# PSoC_PyunPyun_Mini.net
KiCad netlist of a schematic drawn in EAGLE
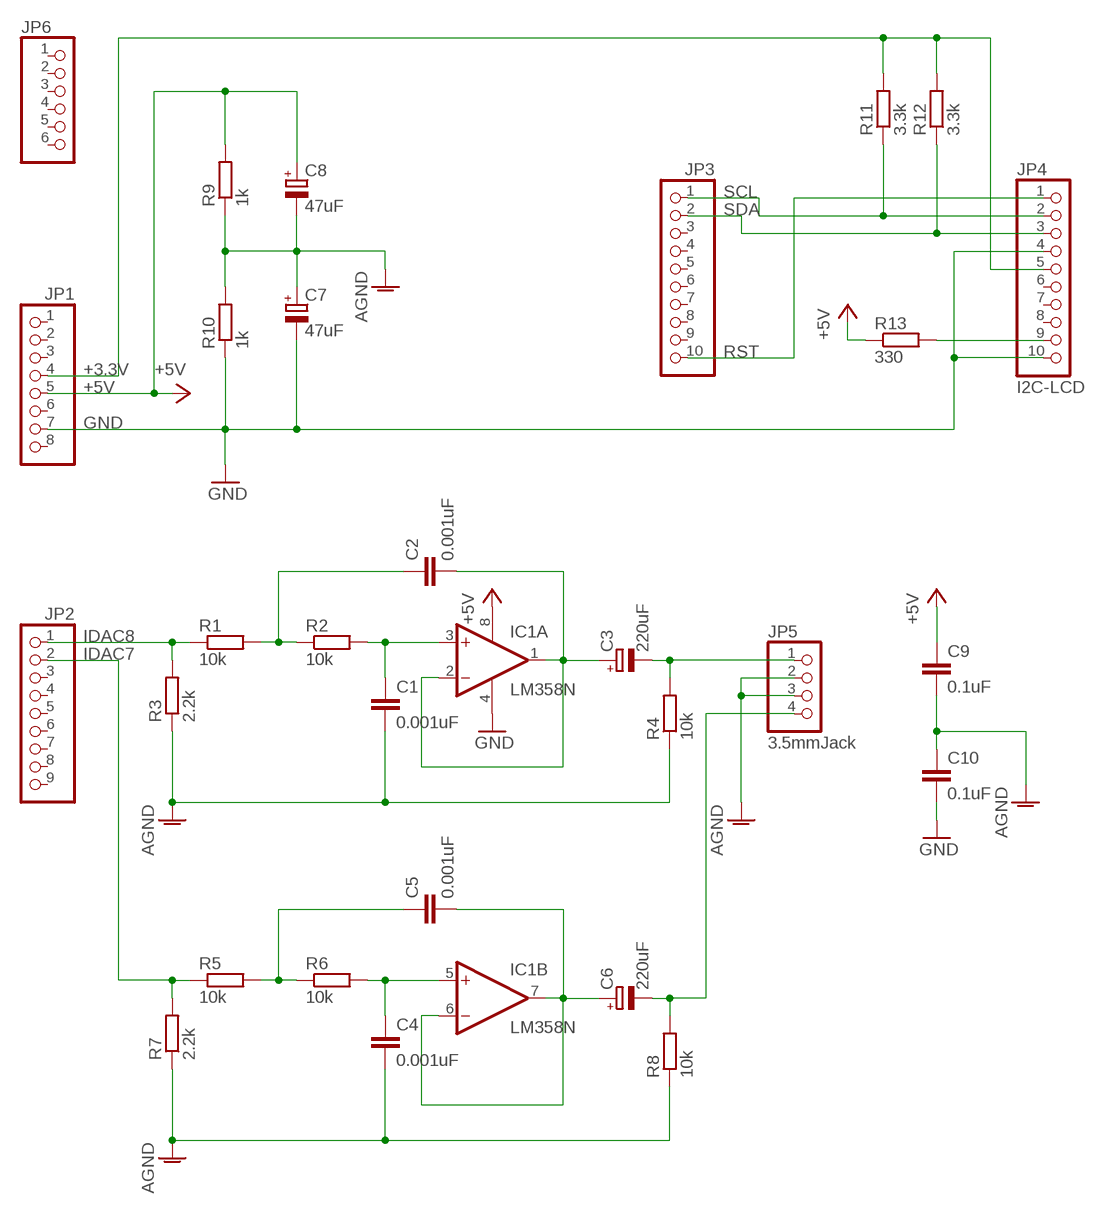
[diagram p0: schematic, sheet 1]

(export (version "E")
  (design (tool "Eeschema 10.0.6"))
  (components
    (comp (ref "C1")
      (value "0.001uF")
      (footprint "eagle-import:C050-024X044")
      (libsource (lib "eagle-import") (part "C-EU050-024X044"))
    )
    (comp (ref "C2")
      (value "0.001uF")
      (footprint "eagle-import:C050-024X044")
      (libsource (lib "eagle-import") (part "C-EU050-024X044"))
    )
    (comp (ref "C3")
      (value "220uF")
      (footprint "eagle-import:E5-8,5")
      (libsource (lib "eagle-import") (part "CPOL-EUE5-8.5"))
    )
    (comp (ref "C4")
      (value "0.001uF")
      (footprint "eagle-import:C050-024X044")
      (libsource (lib "eagle-import") (part "C-EU050-024X044"))
    )
    (comp (ref "C5")
      (value "0.001uF")
      (footprint "eagle-import:C050-024X044")
      (libsource (lib "eagle-import") (part "C-EU050-024X044"))
    )
    (comp (ref "C6")
      (value "220uF")
      (footprint "eagle-import:E5-8,5")
      (libsource (lib "eagle-import") (part "CPOL-EUE5-8.5"))
    )
    (comp (ref "C7")
      (value "47uF")
      (footprint "eagle-import:E5-5")
      (libsource (lib "eagle-import") (part "CPOL-EUE5-5"))
    )
    (comp (ref "C8")
      (value "47uF")
      (footprint "eagle-import:E5-5")
      (libsource (lib "eagle-import") (part "CPOL-EUE5-5"))
    )
    (comp (ref "C9")
      (value "0.1uF")
      (footprint "eagle-import:C050-024X044")
      (libsource (lib "eagle-import") (part "C-EU050-024X044"))
    )
    (comp (ref "C10")
      (value "0.1uF")
      (footprint "eagle-import:C050-024X044")
      (libsource (lib "eagle-import") (part "C-EU050-024X044"))
    )
    (comp (ref "IC1")
      (value "LM358N")
      (footprint "eagle-import:DIL08")
      (libsource (lib "eagle-import") (part "LM358N"))
    )
    (comp (ref "JP1")
      (value "PINHD-1X8")
      (footprint "eagle-import:1X08")
      (libsource (lib "eagle-import") (part "PINHD-1X8"))
    )
    (comp (ref "JP2")
      (value "PINHD-1X9")
      (footprint "eagle-import:1X09")
      (libsource (lib "eagle-import") (part "PINHD-1X9"))
    )
    (comp (ref "JP3")
      (value "PINHD-1X10")
      (footprint "eagle-import:1X10")
      (libsource (lib "eagle-import") (part "PINHD-1X10"))
    )
    (comp (ref "JP4")
      (value "I2C-LCD")
      (footprint "eagle-import:1X10")
      (libsource (lib "eagle-import") (part "PINHD-1X10"))
    )
    (comp (ref "JP5")
      (value "3.5mmJack")
      (footprint "eagle-import:1X04")
      (libsource (lib "eagle-import") (part "PINHD-1X4"))
    )
    (comp (ref "JP6")
      (value "PINHD-1X6")
      (footprint "eagle-import:1X06")
      (libsource (lib "eagle-import") (part "PINHD-1X6"))
    )
    (comp (ref "R1")
      (value "10k")
      (footprint "eagle-import:0207_7")
      (libsource (lib "eagle-import") (part "R-EU_0207/7"))
    )
    (comp (ref "R2")
      (value "10k")
      (footprint "eagle-import:0207_7")
      (libsource (lib "eagle-import") (part "R-EU_0207/7"))
    )
    (comp (ref "R3")
      (value "2.2k")
      (footprint "eagle-import:0207_7")
      (libsource (lib "eagle-import") (part "R-EU_0207/7"))
    )
    (comp (ref "R4")
      (value "10k")
      (footprint "eagle-import:0207_7")
      (libsource (lib "eagle-import") (part "R-EU_0207/7"))
    )
    (comp (ref "R5")
      (value "10k")
      (footprint "eagle-import:0207_7")
      (libsource (lib "eagle-import") (part "R-EU_0207/7"))
    )
    (comp (ref "R6")
      (value "10k")
      (footprint "eagle-import:0207_7")
      (libsource (lib "eagle-import") (part "R-EU_0207/7"))
    )
    (comp (ref "R7")
      (value "2.2k")
      (footprint "eagle-import:0207_7")
      (libsource (lib "eagle-import") (part "R-EU_0207/7"))
    )
    (comp (ref "R8")
      (value "10k")
      (footprint "eagle-import:0207_7")
      (libsource (lib "eagle-import") (part "R-EU_0207/7"))
    )
    (comp (ref "R9")
      (value "1k")
      (footprint "eagle-import:0207_7")
      (libsource (lib "eagle-import") (part "R-EU_0207/7"))
    )
    (comp (ref "R10")
      (value "1k")
      (footprint "eagle-import:0207_7")
      (libsource (lib "eagle-import") (part "R-EU_0207/7"))
    )
    (comp (ref "R11")
      (value "3.3k")
      (footprint "eagle-import:0207_7")
      (libsource (lib "eagle-import") (part "R-EU_0207/7"))
    )
    (comp (ref "R12")
      (value "3.3k")
      (footprint "eagle-import:0207_7")
      (libsource (lib "eagle-import") (part "R-EU_0207/7"))
    )
    (comp (ref "R13")
      (value "330")
      (footprint "eagle-import:0207_7")
      (libsource (lib "eagle-import") (part "R-EU_0207/7"))
    )
  )
  (nets
    (net (code "1") (name "+5V") (class "Default")
      (node (ref "C8") (pin "+") (pinfunction "+_+") (pintype "passive"))
      (node (ref "C9") (pin "1") (pinfunction "1_1") (pintype "passive"))
      (node (ref "IC1") (pin "8") (pinfunction "V+_8") (pintype "power_in"))
      (node (ref "JP1") (pin "5") (pinfunction "5_5") (pintype "passive"))
      (node (ref "R13") (pin "1") (pinfunction "1_1") (pintype "passive"))
      (node (ref "R9") (pin "2") (pinfunction "2_2") (pintype "passive"))
    )
    (net (code "2") (name "/+3.3V") (class "Default")
      (node (ref "JP1") (pin "4") (pinfunction "4_4") (pintype "passive"))
      (node (ref "JP4") (pin "5") (pinfunction "5_5") (pintype "passive"))
      (node (ref "R11") (pin "2") (pinfunction "2_2") (pintype "passive"))
      (node (ref "R12") (pin "2") (pinfunction "2_2") (pintype "passive"))
    )
    (net (code "3") (name "/IDAC7") (class "Default")
      (node (ref "JP2") (pin "2") (pinfunction "2_2") (pintype "passive"))
      (node (ref "R5") (pin "1") (pinfunction "1_1") (pintype "passive"))
      (node (ref "R7") (pin "2") (pinfunction "2_2") (pintype "passive"))
    )
    (net (code "4") (name "/IDAC8") (class "Default")
      (node (ref "JP2") (pin "1") (pinfunction "1_1") (pintype "passive"))
      (node (ref "R1") (pin "1") (pinfunction "1_1") (pintype "passive"))
      (node (ref "R3") (pin "2") (pinfunction "2_2") (pintype "passive"))
    )
    (net (code "5") (name "/RST") (class "Default")
      (node (ref "JP3") (pin "10") (pinfunction "10_10") (pintype "passive"))
      (node (ref "JP4") (pin "1") (pinfunction "1_1") (pintype "passive"))
    )
    (net (code "6") (name "/SCL") (class "Default")
      (node (ref "JP3") (pin "1") (pinfunction "1_1") (pintype "passive"))
      (node (ref "JP4") (pin "2") (pinfunction "2_2") (pintype "passive"))
      (node (ref "R11") (pin "1") (pinfunction "1_1") (pintype "passive"))
    )
    (net (code "7") (name "/SDA") (class "Default")
      (node (ref "JP3") (pin "2") (pinfunction "2_2") (pintype "passive"))
      (node (ref "JP4") (pin "3") (pinfunction "3_3") (pintype "passive"))
      (node (ref "R12") (pin "1") (pinfunction "1_1") (pintype "passive"))
    )
    (net (code "8") (name "AGND") (class "Default")
      (node (ref "C1") (pin "2") (pinfunction "2_2") (pintype "passive"))
      (node (ref "C10") (pin "1") (pinfunction "1_1") (pintype "passive"))
      (node (ref "C4") (pin "2") (pinfunction "2_2") (pintype "passive"))
      (node (ref "C7") (pin "+") (pinfunction "+_+") (pintype "passive"))
      (node (ref "C8") (pin "-") (pinfunction "-_-") (pintype "passive"))
      (node (ref "C9") (pin "2") (pinfunction "2_2") (pintype "passive"))
      (node (ref "JP5") (pin "2") (pinfunction "2_2") (pintype "passive"))
      (node (ref "JP5") (pin "3") (pinfunction "3_3") (pintype "passive"))
      (node (ref "R10") (pin "2") (pinfunction "2_2") (pintype "passive"))
      (node (ref "R3") (pin "1") (pinfunction "1_1") (pintype "passive"))
      (node (ref "R4") (pin "1") (pinfunction "1_1") (pintype "passive"))
      (node (ref "R7") (pin "1") (pinfunction "1_1") (pintype "passive"))
      (node (ref "R8") (pin "1") (pinfunction "1_1") (pintype "passive"))
      (node (ref "R9") (pin "1") (pinfunction "1_1") (pintype "passive"))
    )
    (net (code "9") (name "GND") (class "Default")
      (node (ref "C10") (pin "2") (pinfunction "2_2") (pintype "passive"))
      (node (ref "C7") (pin "-") (pinfunction "-_-") (pintype "passive"))
      (node (ref "IC1") (pin "4") (pinfunction "V-_4") (pintype "power_in"))
      (node (ref "JP1") (pin "7") (pinfunction "7_7") (pintype "passive"))
      (node (ref "JP4") (pin "10") (pinfunction "10_10") (pintype "passive"))
      (node (ref "JP4") (pin "4") (pinfunction "4_4") (pintype "passive"))
      (node (ref "R10") (pin "1") (pinfunction "1_1") (pintype "passive"))
    )
    (net (code "10") (name "Net-(C2-Pad1)") (class "Default")
      (node (ref "C2") (pin "1") (pinfunction "1_1") (pintype "passive"))
      (node (ref "R1") (pin "2") (pinfunction "2_2") (pintype "passive"))
      (node (ref "R2") (pin "1") (pinfunction "1_1") (pintype "passive"))
    )
    (net (code "11") (name "Net-(C3-Pad-)") (class "Default")
      (node (ref "C3") (pin "-") (pinfunction "-_-") (pintype "passive"))
      (node (ref "JP5") (pin "1") (pinfunction "1_1") (pintype "passive"))
      (node (ref "R4") (pin "2") (pinfunction "2_2") (pintype "passive"))
    )
    (net (code "12") (name "Net-(C5-Pad1)") (class "Default")
      (node (ref "C5") (pin "1") (pinfunction "1_1") (pintype "passive"))
      (node (ref "R5") (pin "2") (pinfunction "2_2") (pintype "passive"))
      (node (ref "R6") (pin "1") (pinfunction "1_1") (pintype "passive"))
    )
    (net (code "13") (name "Net-(C6-Pad-)") (class "Default")
      (node (ref "C6") (pin "-") (pinfunction "-_-") (pintype "passive"))
      (node (ref "JP5") (pin "4") (pinfunction "4_4") (pintype "passive"))
      (node (ref "R8") (pin "2") (pinfunction "2_2") (pintype "passive"))
    )
    (net (code "14") (name "Net-(IC1A-+IN)") (class "Default")
      (node (ref "C1") (pin "1") (pinfunction "1_1") (pintype "passive"))
      (node (ref "IC1") (pin "3") (pinfunction "+IN_3") (pintype "input"))
      (node (ref "R2") (pin "2") (pinfunction "2_2") (pintype "passive"))
    )
    (net (code "15") (name "Net-(IC1A--IN)") (class "Default")
      (node (ref "C2") (pin "2") (pinfunction "2_2") (pintype "passive"))
      (node (ref "C3") (pin "+") (pinfunction "+_+") (pintype "passive"))
      (node (ref "IC1") (pin "1") (pinfunction "OUT_1") (pintype "output"))
      (node (ref "IC1") (pin "2") (pinfunction "-IN_2") (pintype "input"))
    )
    (net (code "16") (name "Net-(IC1B-+IN)") (class "Default")
      (node (ref "C4") (pin "1") (pinfunction "1_1") (pintype "passive"))
      (node (ref "IC1") (pin "5") (pinfunction "+IN_5") (pintype "input"))
      (node (ref "R6") (pin "2") (pinfunction "2_2") (pintype "passive"))
    )
    (net (code "17") (name "Net-(IC1B--IN)") (class "Default")
      (node (ref "C5") (pin "2") (pinfunction "2_2") (pintype "passive"))
      (node (ref "C6") (pin "+") (pinfunction "+_+") (pintype "passive"))
      (node (ref "IC1") (pin "6") (pinfunction "-IN_6") (pintype "input"))
      (node (ref "IC1") (pin "7") (pinfunction "OUT_7") (pintype "output"))
    )
    (net (code "18") (name "Net-(JP4-Pad9)") (class "Default")
      (node (ref "JP4") (pin "9") (pinfunction "9_9") (pintype "passive"))
      (node (ref "R13") (pin "2") (pinfunction "2_2") (pintype "passive"))
    )
    (net (code "19") (name "unconnected-(JP1-Pad1)") (class "Default")
      (node (ref "JP1") (pin "1") (pinfunction "1_1") (pintype "passive"))
    )
    (net (code "20") (name "unconnected-(JP1-Pad2)") (class "Default")
      (node (ref "JP1") (pin "2") (pinfunction "2_2") (pintype "passive"))
    )
    (net (code "21") (name "unconnected-(JP1-Pad3)") (class "Default")
      (node (ref "JP1") (pin "3") (pinfunction "3_3") (pintype "passive"))
    )
    (net (code "22") (name "unconnected-(JP1-Pad6)") (class "Default")
      (node (ref "JP1") (pin "6") (pinfunction "6_6") (pintype "passive"))
    )
    (net (code "23") (name "unconnected-(JP1-Pad8)") (class "Default")
      (node (ref "JP1") (pin "8") (pinfunction "8_8") (pintype "passive"))
    )
    (net (code "24") (name "unconnected-(JP2-Pad3)") (class "Default")
      (node (ref "JP2") (pin "3") (pinfunction "3_3") (pintype "passive"))
    )
    (net (code "25") (name "unconnected-(JP2-Pad4)") (class "Default")
      (node (ref "JP2") (pin "4") (pinfunction "4_4") (pintype "passive"))
    )
    (net (code "26") (name "unconnected-(JP2-Pad5)") (class "Default")
      (node (ref "JP2") (pin "5") (pinfunction "5_5") (pintype "passive"))
    )
    (net (code "27") (name "unconnected-(JP2-Pad6)") (class "Default")
      (node (ref "JP2") (pin "6") (pinfunction "6_6") (pintype "passive"))
    )
    (net (code "28") (name "unconnected-(JP2-Pad7)") (class "Default")
      (node (ref "JP2") (pin "7") (pinfunction "7_7") (pintype "passive"))
    )
    (net (code "29") (name "unconnected-(JP2-Pad8)") (class "Default")
      (node (ref "JP2") (pin "8") (pinfunction "8_8") (pintype "passive"))
    )
    (net (code "30") (name "unconnected-(JP2-Pad9)") (class "Default")
      (node (ref "JP2") (pin "9") (pinfunction "9_9") (pintype "passive"))
    )
    (net (code "31") (name "unconnected-(JP3-Pad3)") (class "Default")
      (node (ref "JP3") (pin "3") (pinfunction "3_3") (pintype "passive"))
    )
    (net (code "32") (name "unconnected-(JP3-Pad4)") (class "Default")
      (node (ref "JP3") (pin "4") (pinfunction "4_4") (pintype "passive"))
    )
    (net (code "33") (name "unconnected-(JP3-Pad5)") (class "Default")
      (node (ref "JP3") (pin "5") (pinfunction "5_5") (pintype "passive"))
    )
    (net (code "34") (name "unconnected-(JP3-Pad6)") (class "Default")
      (node (ref "JP3") (pin "6") (pinfunction "6_6") (pintype "passive"))
    )
    (net (code "35") (name "unconnected-(JP3-Pad7)") (class "Default")
      (node (ref "JP3") (pin "7") (pinfunction "7_7") (pintype "passive"))
    )
    (net (code "36") (name "unconnected-(JP3-Pad8)") (class "Default")
      (node (ref "JP3") (pin "8") (pinfunction "8_8") (pintype "passive"))
    )
    (net (code "37") (name "unconnected-(JP3-Pad9)") (class "Default")
      (node (ref "JP3") (pin "9") (pinfunction "9_9") (pintype "passive"))
    )
    (net (code "38") (name "unconnected-(JP4-Pad6)") (class "Default")
      (node (ref "JP4") (pin "6") (pinfunction "6_6") (pintype "passive"))
    )
    (net (code "39") (name "unconnected-(JP4-Pad7)") (class "Default")
      (node (ref "JP4") (pin "7") (pinfunction "7_7") (pintype "passive"))
    )
    (net (code "40") (name "unconnected-(JP4-Pad8)") (class "Default")
      (node (ref "JP4") (pin "8") (pinfunction "8_8") (pintype "passive"))
    )
    (net (code "41") (name "unconnected-(JP6-Pad1)") (class "Default")
      (node (ref "JP6") (pin "1") (pinfunction "1_1") (pintype "passive"))
    )
    (net (code "42") (name "unconnected-(JP6-Pad2)") (class "Default")
      (node (ref "JP6") (pin "2") (pinfunction "2_2") (pintype "passive"))
    )
    (net (code "43") (name "unconnected-(JP6-Pad3)") (class "Default")
      (node (ref "JP6") (pin "3") (pinfunction "3_3") (pintype "passive"))
    )
    (net (code "44") (name "unconnected-(JP6-Pad4)") (class "Default")
      (node (ref "JP6") (pin "4") (pinfunction "4_4") (pintype "passive"))
    )
    (net (code "45") (name "unconnected-(JP6-Pad5)") (class "Default")
      (node (ref "JP6") (pin "5") (pinfunction "5_5") (pintype "passive"))
    )
    (net (code "46") (name "unconnected-(JP6-Pad6)") (class "Default")
      (node (ref "JP6") (pin "6") (pinfunction "6_6") (pintype "passive"))
    )
  )
)
